# DistanceSensorBottom.net
KiCad netlist of a schematic drawn in Altium Designer
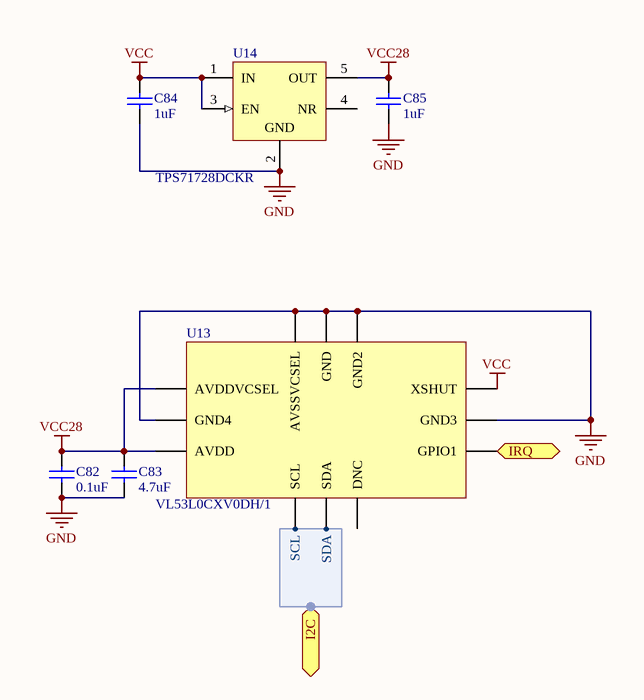
[diagram p0: DistanceSensorBottom.SchDoc]

(export (version "E")
  (design (tool "Eeschema 10.0.6"))
  (components
    (comp (ref "C82")
      (value "0.1uF")
      (footprint "C0402[1005X55]")
      (description "0.1uF 6.3V 10% 0402 (1005 Metric)")
      (fields (field (name "PARTNUMBER") "GRM155R70J104KA01D") (field (name "MANUFACTURER") "Murata"))
      (libsource (lib "Capacitors") (part "CAP_0.1uF_6.3V_0402_10%"))
    )
    (comp (ref "C83")
      (value "4.7uF")
      (footprint "C0402[1005X55]")
      (description "4.7uF 6.3V 20% 0402 (1005 Metric)")
      (fields (field (name "PARTNUMBER") "GRM155R60J475ME47D") (field (name "MANUFACTURER") "Murata"))
      (libsource (lib "Capacitors") (part "CAP_4.7uF_6.3V_0402_20%"))
    )
    (comp (ref "C84")
      (value "1uF")
      (footprint "C0402[1005X55]")
      (description "1uF 6.3V 10% 0402 (1005 Metric)")
      (fields (field (name "PARTNUMBER") "GRM155R70J105KA12D") (field (name "MANUFACTURER") "Murata"))
      (libsource (lib "Capacitors") (part "CAP_1uF_6.3V_0402_10%"))
    )
    (comp (ref "C85")
      (value "1uF")
      (footprint "C0402[1005X55]")
      (description "1uF 6.3V 10% 0402 (1005 Metric)")
      (fields (field (name "PARTNUMBER") "GRM155R70J105KA12D") (field (name "MANUFACTURER") "Murata"))
      (libsource (lib "Capacitors") (part "CAP_1uF_6.3V_0402_10%"))
    )
    (comp (ref "U13")
      (value "VL53L0CXV0DH/1")
      (footprint "LGA-12")
      (description "Optical Sensor Modules Time-of-Flight (ToF) ranging sensor")
      (fields (field (name "MANUFACTURER") "STMicroelectronics"))
      (libsource (lib "ICs") (part "VL53L0CXV0DH/1"))
    )
    (comp (ref "U14")
      (value "TPS71728DCKR")
      (footprint "DCK0005A_L")
      (fields (field (name "MANUFACTURER") "Texas Instruments"))
      (libsource (lib "Altium Content Vault") (part "TI-TPS79NXX-YYSOT5"))
    )
  )
  (nets
    (net (code "2") (name "/IRQ") (class "Default")
      (node (ref "U13") (pin "7") (pinfunction "GPIO1_7") (pintype "passive"))
    )
    (net (code "3") (name "/SCL") (class "Default")
      (node (ref "U13") (pin "10") (pinfunction "SCL_10") (pintype "passive"))
    )
    (net (code "4") (name "/SDA") (class "Default")
      (node (ref "U13") (pin "9") (pinfunction "SDA_9") (pintype "passive"))
    )
    (net (code "6") (name "GND") (class "Default")
      (node (ref "C82") (pin "1") (pinfunction "1_1") (pintype "passive"))
      (node (ref "C83") (pin "1") (pinfunction "1_1") (pintype "passive"))
      (node (ref "C84") (pin "1") (pinfunction "1_1") (pintype "passive"))
      (node (ref "C85") (pin "1") (pinfunction "1_1") (pintype "passive"))
      (node (ref "U13") (pin "12") (pinfunction "GND4_12") (pintype "passive"))
      (node (ref "U13") (pin "2") (pinfunction "AVSSVCSEL_2") (pintype "passive"))
      (node (ref "U13") (pin "3") (pinfunction "GND_3") (pintype "passive"))
      (node (ref "U13") (pin "4") (pinfunction "GND2_4") (pintype "passive"))
      (node (ref "U13") (pin "6") (pinfunction "GND3_6") (pintype "passive"))
      (node (ref "U14") (pin "2") (pinfunction "GND_2") (pintype "power_in"))
    )
    (net (code "7") (name "VCC") (class "Default")
      (node (ref "C84") (pin "2") (pinfunction "2_2") (pintype "passive"))
      (node (ref "U13") (pin "5") (pinfunction "XSHUT_5") (pintype "passive"))
      (node (ref "U14") (pin "1") (pinfunction "IN_1") (pintype "power_in"))
      (node (ref "U14") (pin "3") (pinfunction "EN_3") (pintype "input"))
    )
    (net (code "8") (name "VCC28") (class "Default")
      (node (ref "C82") (pin "2") (pinfunction "2_2") (pintype "passive"))
      (node (ref "C83") (pin "2") (pinfunction "2_2") (pintype "passive"))
      (node (ref "C85") (pin "2") (pinfunction "2_2") (pintype "passive"))
      (node (ref "U13") (pin "1") (pinfunction "AVDDVCSEL_1") (pintype "passive"))
      (node (ref "U13") (pin "11") (pinfunction "AVDD_11") (pintype "passive"))
      (node (ref "U14") (pin "5") (pinfunction "OUT_5") (pintype "power_in"))
    )
    (net (code "9") (name "unconnected-(U13-DNC-Pad8)") (class "Default")
      (node (ref "U13") (pin "8") (pinfunction "DNC_8") (pintype "passive"))
    )
    (net (code "10") (name "unconnected-(U14-NR-Pad4)") (class "Default")
      (node (ref "U14") (pin "4") (pinfunction "NR_4") (pintype "passive"))
    )
  )
)
